# spacecam.net
KiCad netlist of a schematic drawn in EAGLE
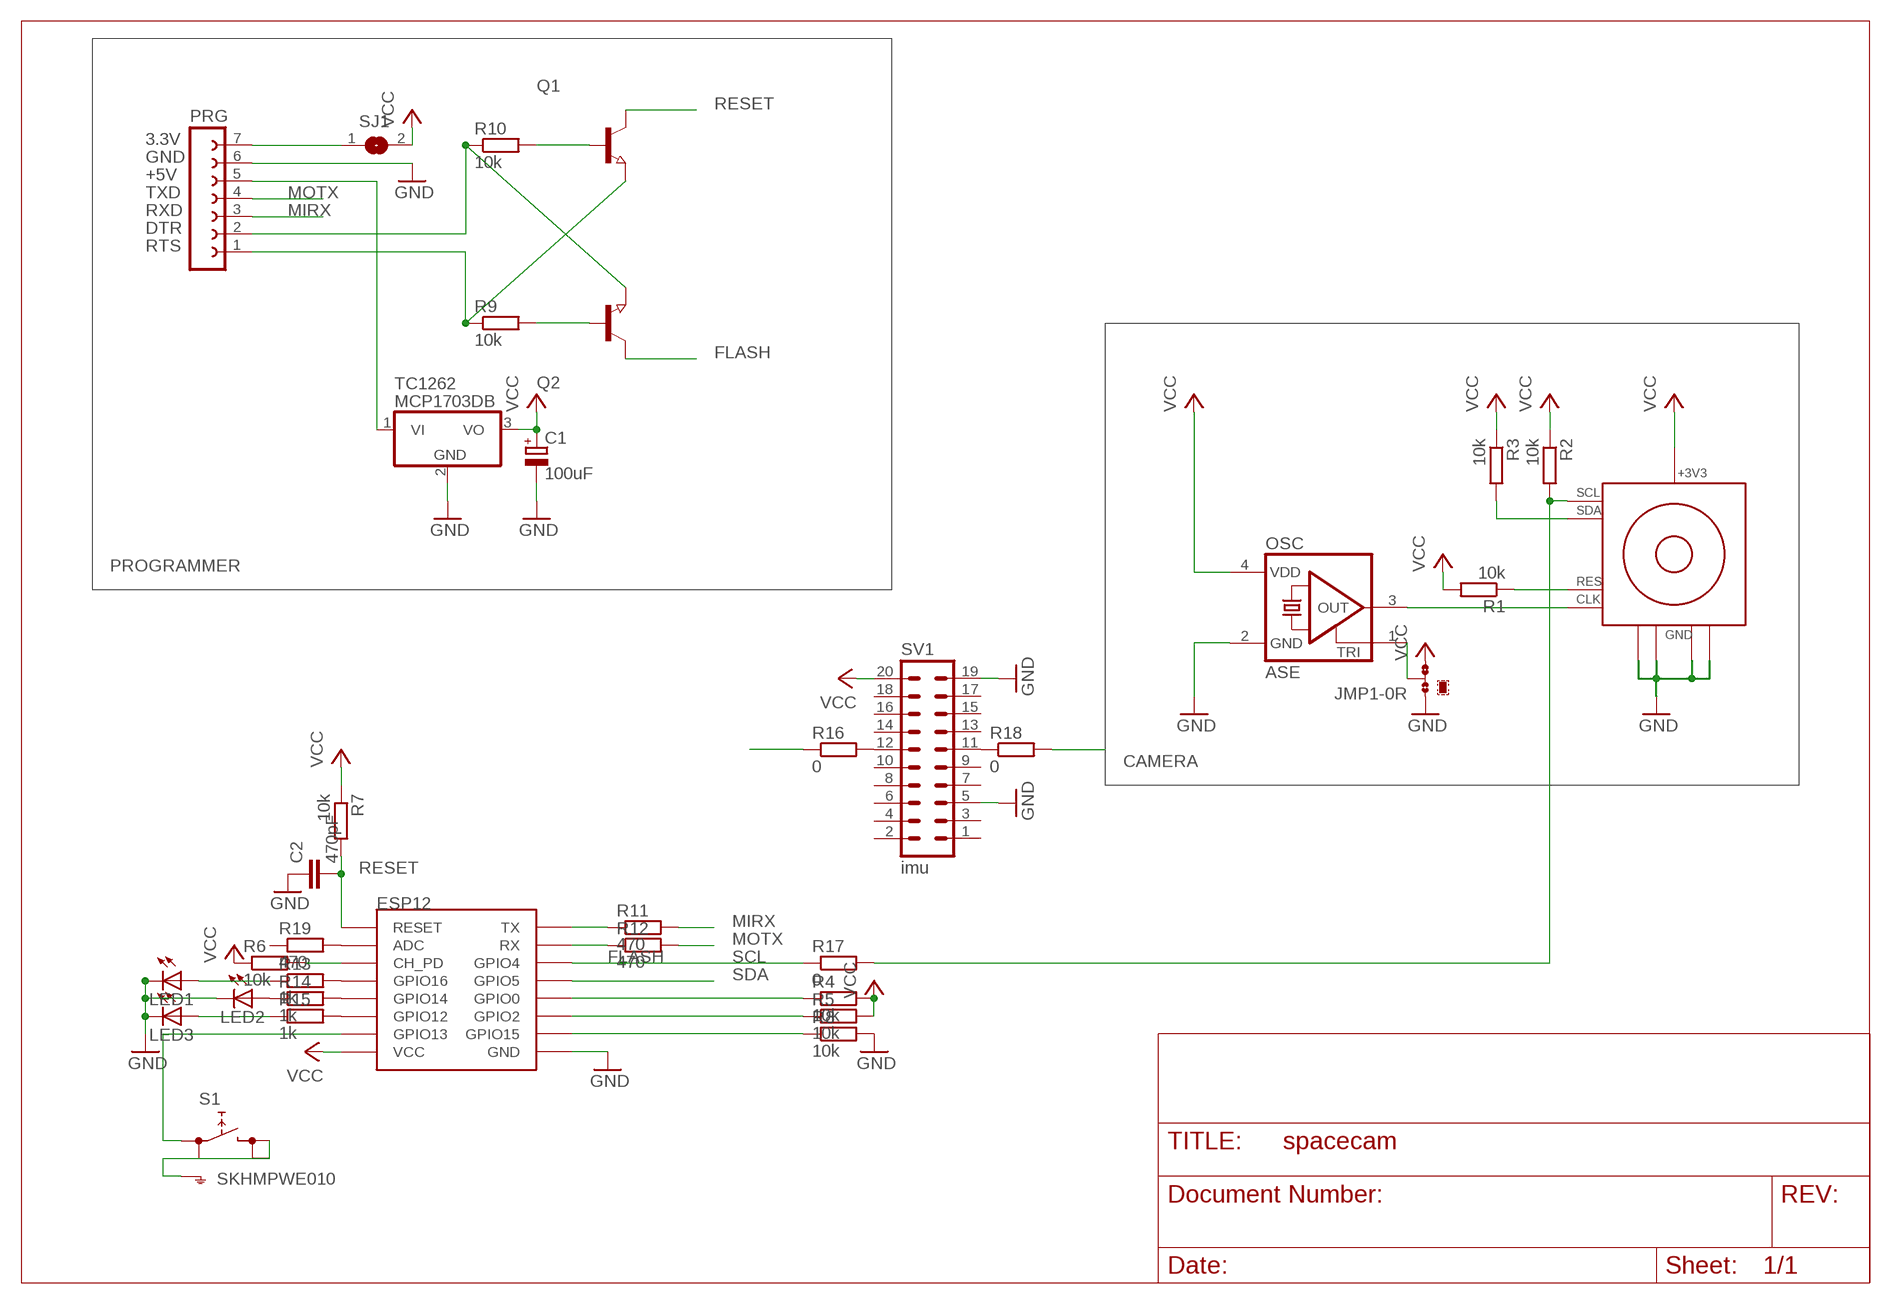
[diagram p0: schematic, sheet 1]

(export (version "E")
  (design (tool "Eeschema 10.0.6"))
  (components
    (comp (ref "C1")
      (value "100uF")
      (footprint "eagle-import:153CLV-0605")
      (libsource (lib "eagle-import") (part "CPOL-EU153CLV-0605"))
    )
    (comp (ref "C2")
      (value "470pF")
      (footprint "eagle-import:C0603")
      (libsource (lib "eagle-import") (part "C-EUC0603"))
    )
    (comp (ref "ESP12")
      (value "ESP12SMD")
      (footprint "eagle-import:ESP12-SMD")
      (libsource (lib "eagle-import") (part "ESP12SMD"))
    )
    (comp (ref "IR1")
      (value "Wiimote IR")
      (footprint "eagle-import:WII_IR_SENSOR")
      (libsource (lib "eagle-import") (part "WII_IR_SENSOR"))
    )
    (comp (ref "JMP1")
      (value "0R-JUMPB")
      (footprint "eagle-import:B0R-JMP")
      (libsource (lib "eagle-import") (part "0R-JUMPB"))
    )
    (comp (ref "LED1")
      (value "LEDSML0603")
      (footprint "eagle-import:SML0603")
      (libsource (lib "eagle-import") (part "LEDSML0603"))
    )
    (comp (ref "LED2")
      (value "LEDSML0603")
      (footprint "eagle-import:SML0603")
      (libsource (lib "eagle-import") (part "LEDSML0603"))
    )
    (comp (ref "LED3")
      (value "LEDSML0603")
      (footprint "eagle-import:SML0603")
      (libsource (lib "eagle-import") (part "LEDSML0603"))
    )
    (comp (ref "OSC")
      (value "ASE")
      (footprint "eagle-import:ASE")
      (libsource (lib "eagle-import") (part "ASE"))
    )
    (comp (ref "PRG")
      (value "FE07-1")
      (footprint "eagle-import:FE07")
      (libsource (lib "eagle-import") (part "FE07-1"))
    )
    (comp (ref "Q1")
      (value "NPN-TRANSISTOR_SOT23")
      (footprint "eagle-import:SOT23")
      (libsource (lib "eagle-import") (part "NPN-TRANSISTOR_SOT23"))
    )
    (comp (ref "Q2")
      (value "NPN-TRANSISTOR_SOT23")
      (footprint "eagle-import:SOT23")
      (libsource (lib "eagle-import") (part "NPN-TRANSISTOR_SOT23"))
    )
    (comp (ref "R1")
      (value "10k")
      (footprint "eagle-import:R0603")
      (libsource (lib "eagle-import") (part "R-EU_R0603"))
    )
    (comp (ref "R2")
      (value "10k")
      (footprint "eagle-import:R0603")
      (libsource (lib "eagle-import") (part "R-EU_R0603"))
    )
    (comp (ref "R3")
      (value "10k")
      (footprint "eagle-import:R0603")
      (libsource (lib "eagle-import") (part "R-EU_R0603"))
    )
    (comp (ref "R4")
      (value "10k")
      (footprint "eagle-import:R0603")
      (libsource (lib "eagle-import") (part "R-EU_R0603"))
    )
    (comp (ref "R5")
      (value "10k")
      (footprint "eagle-import:R0603")
      (libsource (lib "eagle-import") (part "R-EU_R0603"))
    )
    (comp (ref "R6")
      (value "10k")
      (footprint "eagle-import:R0603")
      (libsource (lib "eagle-import") (part "R-EU_R0603"))
    )
    (comp (ref "R7")
      (value "10k")
      (footprint "eagle-import:R0603")
      (libsource (lib "eagle-import") (part "R-EU_R0603"))
    )
    (comp (ref "R8")
      (value "10k")
      (footprint "eagle-import:R0603")
      (libsource (lib "eagle-import") (part "R-EU_R0603"))
    )
    (comp (ref "R9")
      (value "10k")
      (footprint "eagle-import:R0603")
      (libsource (lib "eagle-import") (part "R-EU_R0603"))
    )
    (comp (ref "R10")
      (value "10k")
      (footprint "eagle-import:R0603")
      (libsource (lib "eagle-import") (part "R-EU_R0603"))
    )
    (comp (ref "R11")
      (value "470")
      (footprint "eagle-import:R0603")
      (libsource (lib "eagle-import") (part "R-EU_R0603"))
    )
    (comp (ref "R12")
      (value "470")
      (footprint "eagle-import:R0603")
      (libsource (lib "eagle-import") (part "R-EU_R0603"))
    )
    (comp (ref "R13")
      (value "1k")
      (footprint "eagle-import:R0603")
      (libsource (lib "eagle-import") (part "R-EU_R0603"))
    )
    (comp (ref "R14")
      (value "1k")
      (footprint "eagle-import:R0603")
      (libsource (lib "eagle-import") (part "R-EU_R0603"))
    )
    (comp (ref "R15")
      (value "1k")
      (footprint "eagle-import:R0603")
      (libsource (lib "eagle-import") (part "R-EU_R0603"))
    )
    (comp (ref "R16")
      (value "0")
      (footprint "eagle-import:R0603")
      (libsource (lib "eagle-import") (part "R-EU_R0603"))
    )
    (comp (ref "R17")
      (value "0")
      (footprint "eagle-import:R0603")
      (libsource (lib "eagle-import") (part "R-EU_R0603"))
    )
    (comp (ref "R18")
      (value "0")
      (footprint "eagle-import:R0603")
      (libsource (lib "eagle-import") (part "R-EU_R0603"))
    )
    (comp (ref "R19")
      (value "470")
      (footprint "eagle-import:R0603")
      (libsource (lib "eagle-import") (part "R-EU_R0603"))
    )
    (comp (ref "S1")
      (value "SKHMPWE010")
      (footprint "eagle-import:SKHMPXE010")
      (libsource (lib "eagle-import") (part "SKHMPE010W"))
    )
    (comp (ref "SJ1") (value "SJ") (footprint "eagle-import:SJ") (libsource (lib "eagle-import") (part "SJ")))
    (comp (ref "SV1")
      (value "imu")
      (footprint "eagle-import:MA10-2")
      (libsource (lib "eagle-import") (part "MA10-2"))
    )
    (comp (ref "TC1262")
      (value "MCP1703DB")
      (footprint "eagle-import:SOT223")
      (libsource (lib "eagle-import") (part "MCP1703DB"))
    )
  )
  (nets
    (net (code "1") (name "/FLASH") (class "Default")
      (node (ref "ESP12") (pin "GPIO0") (pinfunction "GPIO0_GPIO0") (pintype "bidirectional"))
      (node (ref "Q2") (pin "3") (pinfunction "C_3") (pintype "passive"))
      (node (ref "R4") (pin "1") (pinfunction "1_1") (pintype "passive"))
    )
    (net (code "2") (name "/MIRX") (class "Default")
      (node (ref "PRG") (pin "3") (pinfunction "3_3") (pintype "passive"))
      (node (ref "R11") (pin "2") (pinfunction "2_2") (pintype "passive"))
    )
    (net (code "3") (name "/MOTX") (class "Default")
      (node (ref "PRG") (pin "4") (pinfunction "4_4") (pintype "passive"))
      (node (ref "R12") (pin "2") (pinfunction "2_2") (pintype "passive"))
    )
    (net (code "4") (name "/RESET") (class "Default")
      (node (ref "C2") (pin "2") (pinfunction "2_2") (pintype "passive"))
      (node (ref "ESP12") (pin "RESET") (pinfunction "RESET_RESET") (pintype "bidirectional"))
      (node (ref "Q1") (pin "3") (pinfunction "C_3") (pintype "passive"))
      (node (ref "R7") (pin "2") (pinfunction "2_2") (pintype "passive"))
    )
    (net (code "5") (name "/SCL") (class "Default")
      (node (ref "ESP12") (pin "GPIO4") (pinfunction "GPIO4_GPIO4") (pintype "bidirectional"))
      (node (ref "R16") (pin "1") (pinfunction "1_1") (pintype "passive"))
      (node (ref "R17") (pin "1") (pinfunction "1_1") (pintype "passive"))
    )
    (net (code "6") (name "/SDA") (class "Default")
      (node (ref "ESP12") (pin "GPIO5") (pinfunction "GPIO5_GPIO5") (pintype "bidirectional"))
      (node (ref "IR1") (pin "6_SDA") (pinfunction "SDA_6_SDA") (pintype "bidirectional"))
      (node (ref "R18") (pin "2") (pinfunction "2_2") (pintype "passive"))
      (node (ref "R3") (pin "2") (pinfunction "2_2") (pintype "passive"))
    )
    (net (code "7") (name "GND") (class "Default")
      (node (ref "C1") (pin "-") (pinfunction "-_-") (pintype "passive"))
      (node (ref "C2") (pin "1") (pinfunction "1_1") (pintype "passive"))
      (node (ref "ESP12") (pin "GND") (pinfunction "GND_GND") (pintype "bidirectional"))
      (node (ref "IR1") (pin "2_GND@1") (pinfunction "GND_2_GND@1") (pintype "bidirectional"))
      (node (ref "IR1") (pin "3_GND@2") (pinfunction "GND_3_GND@2") (pintype "bidirectional"))
      (node (ref "IR1") (pin "GND@3") (pinfunction "GND_GND@3") (pintype "bidirectional"))
      (node (ref "IR1") (pin "GND@4") (pinfunction "GND_GND@4") (pintype "bidirectional"))
      (node (ref "JMP1") (pin "1") (pinfunction "1_1") (pintype "passive"))
      (node (ref "LED1") (pin "C") (pinfunction "C_C") (pintype "passive"))
      (node (ref "LED2") (pin "C") (pinfunction "C_C") (pintype "passive"))
      (node (ref "LED3") (pin "C") (pinfunction "C_C") (pintype "passive"))
      (node (ref "OSC") (pin "2") (pinfunction "GND_2") (pintype "power_in"))
      (node (ref "PRG") (pin "6") (pinfunction "6_6") (pintype "passive"))
      (node (ref "R8") (pin "2") (pinfunction "2_2") (pintype "passive"))
      (node (ref "S1") (pin "2") (pinfunction "1.2_2") (pintype "passive"))
      (node (ref "S1") (pin "3") (pinfunction "2.1_3") (pintype "passive"))
      (node (ref "S1") (pin "4") (pinfunction "2.2_4") (pintype "passive"))
      (node (ref "S1") (pin "5") (pinfunction "SH_5") (pintype "passive"))
      (node (ref "SV1") (pin "19") (pinfunction "19_19") (pintype "passive"))
      (node (ref "SV1") (pin "5") (pinfunction "5_5") (pintype "passive"))
      (node (ref "TC1262") (pin "2") (pinfunction "GND_2") (pintype "passive"))
    )
    (net (code "8") (name "Net-(ESP12-PadADC)") (class "Default")
      (node (ref "ESP12") (pin "ADC") (pinfunction "ADC_ADC") (pintype "bidirectional"))
      (node (ref "R19") (pin "2") (pinfunction "2_2") (pintype "passive"))
    )
    (net (code "9") (name "Net-(ESP12-PadCH_PD)") (class "Default")
      (node (ref "ESP12") (pin "CH_PD") (pinfunction "CH_PD_CH_PD") (pintype "bidirectional"))
      (node (ref "R6") (pin "2") (pinfunction "2_2") (pintype "passive"))
    )
    (net (code "10") (name "Net-(ESP12-PadGPIO2)") (class "Default")
      (node (ref "ESP12") (pin "GPIO2") (pinfunction "GPIO2_GPIO2") (pintype "bidirectional"))
      (node (ref "R5") (pin "1") (pinfunction "1_1") (pintype "passive"))
    )
    (net (code "11") (name "Net-(ESP12-PadGPIO12)") (class "Default")
      (node (ref "ESP12") (pin "GPIO12") (pinfunction "GPIO12_GPIO12") (pintype "bidirectional"))
      (node (ref "R15") (pin "2") (pinfunction "2_2") (pintype "passive"))
    )
    (net (code "12") (name "Net-(ESP12-PadGPIO14)") (class "Default")
      (node (ref "ESP12") (pin "GPIO14") (pinfunction "GPIO14_GPIO14") (pintype "bidirectional"))
      (node (ref "R14") (pin "2") (pinfunction "2_2") (pintype "passive"))
    )
    (net (code "13") (name "Net-(ESP12-PadGPIO15)") (class "Default")
      (node (ref "ESP12") (pin "GPIO15") (pinfunction "GPIO15_GPIO15") (pintype "bidirectional"))
      (node (ref "R8") (pin "1") (pinfunction "1_1") (pintype "passive"))
    )
    (net (code "14") (name "Net-(ESP12-PadGPIO16)") (class "Default")
      (node (ref "ESP12") (pin "GPIO16") (pinfunction "GPIO16_GPIO16") (pintype "bidirectional"))
      (node (ref "R13") (pin "2") (pinfunction "2_2") (pintype "passive"))
    )
    (net (code "15") (name "Net-(ESP12-RX)") (class "Default")
      (node (ref "ESP12") (pin "RXD0") (pinfunction "RX_RXD0") (pintype "bidirectional"))
      (node (ref "R12") (pin "1") (pinfunction "1_1") (pintype "passive"))
    )
    (net (code "16") (name "Net-(ESP12-TX)") (class "Default")
      (node (ref "ESP12") (pin "TXD0") (pinfunction "TX_TXD0") (pintype "bidirectional"))
      (node (ref "R11") (pin "1") (pinfunction "1_1") (pintype "passive"))
    )
    (net (code "17") (name "Net-(IR1-CLK)") (class "Default")
      (node (ref "IR1") (pin "7_CLK") (pinfunction "CLK_7_CLK") (pintype "bidirectional"))
      (node (ref "OSC") (pin "3") (pinfunction "OUT_3") (pintype "output"))
    )
    (net (code "18") (name "Net-(IR1-RES)") (class "Default")
      (node (ref "IR1") (pin "8_RESET") (pinfunction "RES_8_RESET") (pintype "bidirectional"))
      (node (ref "R1") (pin "1") (pinfunction "1_1") (pintype "passive"))
    )
    (net (code "19") (name "Net-(IR1-SCL)") (class "Default")
      (node (ref "IR1") (pin "5_SCL") (pinfunction "SCL_5_SCL") (pintype "bidirectional"))
      (node (ref "R17") (pin "2") (pinfunction "2_2") (pintype "passive"))
      (node (ref "R2") (pin "2") (pinfunction "2_2") (pintype "passive"))
    )
    (net (code "20") (name "Net-(LED1-PadA)") (class "Default")
      (node (ref "LED1") (pin "A") (pinfunction "A_A") (pintype "passive"))
      (node (ref "R13") (pin "1") (pinfunction "1_1") (pintype "passive"))
    )
    (net (code "21") (name "Net-(LED2-PadA)") (class "Default")
      (node (ref "LED2") (pin "A") (pinfunction "A_A") (pintype "passive"))
      (node (ref "R14") (pin "1") (pinfunction "1_1") (pintype "passive"))
    )
    (net (code "22") (name "Net-(LED3-PadA)") (class "Default")
      (node (ref "LED3") (pin "A") (pinfunction "A_A") (pintype "passive"))
      (node (ref "R15") (pin "1") (pinfunction "1_1") (pintype "passive"))
    )
    (net (code "23") (name "Net-(OSC-TRI)") (class "Default")
      (node (ref "JMP1") (pin "2") (pinfunction "2_2") (pintype "passive"))
      (node (ref "OSC") (pin "1") (pinfunction "TRI_1") (pintype "input"))
    )
    (net (code "24") (name "Net-(PRG-Pad7)") (class "Default")
      (node (ref "PRG") (pin "7") (pinfunction "7_7") (pintype "passive"))
      (node (ref "SJ1") (pin "1") (pinfunction "1_1") (pintype "passive"))
    )
    (net (code "25") (name "Net-(Q1-B)") (class "Default")
      (node (ref "Q1") (pin "1") (pinfunction "B_1") (pintype "passive"))
      (node (ref "R10") (pin "2") (pinfunction "2_2") (pintype "passive"))
    )
    (net (code "26") (name "Net-(Q1-E)") (class "Default")
      (node (ref "PRG") (pin "1") (pinfunction "1_1") (pintype "passive"))
      (node (ref "Q1") (pin "2") (pinfunction "E_2") (pintype "passive"))
      (node (ref "R9") (pin "1") (pinfunction "1_1") (pintype "passive"))
    )
    (net (code "27") (name "Net-(Q2-B)") (class "Default")
      (node (ref "Q2") (pin "1") (pinfunction "B_1") (pintype "passive"))
      (node (ref "R9") (pin "2") (pinfunction "2_2") (pintype "passive"))
    )
    (net (code "28") (name "Net-(Q2-E)") (class "Default")
      (node (ref "PRG") (pin "2") (pinfunction "2_2") (pintype "passive"))
      (node (ref "Q2") (pin "2") (pinfunction "E_2") (pintype "passive"))
      (node (ref "R10") (pin "1") (pinfunction "1_1") (pintype "passive"))
    )
    (net (code "29") (name "Net-(R16-Pad2)") (class "Default")
      (node (ref "R16") (pin "2") (pinfunction "2_2") (pintype "passive"))
      (node (ref "SV1") (pin "12") (pinfunction "12_12") (pintype "passive"))
    )
    (net (code "30") (name "Net-(R18-Pad1)") (class "Default")
      (node (ref "R18") (pin "1") (pinfunction "1_1") (pintype "passive"))
      (node (ref "SV1") (pin "11") (pinfunction "11_11") (pintype "passive"))
    )
    (net (code "31") (name "Net-(S1-1.1)") (class "Default")
      (node (ref "ESP12") (pin "GPIO13") (pinfunction "GPIO13_GPIO13") (pintype "bidirectional"))
      (node (ref "S1") (pin "1") (pinfunction "1.1_1") (pintype "passive"))
    )
    (net (code "32") (name "Net-(TC1262-VI)") (class "Default")
      (node (ref "PRG") (pin "5") (pinfunction "5_5") (pintype "passive"))
      (node (ref "TC1262") (pin "1") (pinfunction "VI_1") (pintype "input"))
    )
    (net (code "33") (name "VCC") (class "Default")
      (node (ref "C1") (pin "+") (pinfunction "+_+") (pintype "passive"))
      (node (ref "ESP12") (pin "VCC") (pinfunction "VCC_VCC") (pintype "bidirectional"))
      (node (ref "IR1") (pin "1_+3V3") (pinfunction "+3V3_1_+3V3") (pintype "bidirectional"))
      (node (ref "JMP1") (pin "3") (pinfunction "3_3") (pintype "passive"))
      (node (ref "OSC") (pin "4") (pinfunction "VDD_4") (pintype "power_in"))
      (node (ref "R1") (pin "2") (pinfunction "2_2") (pintype "passive"))
      (node (ref "R2") (pin "1") (pinfunction "1_1") (pintype "passive"))
      (node (ref "R3") (pin "1") (pinfunction "1_1") (pintype "passive"))
      (node (ref "R4") (pin "2") (pinfunction "2_2") (pintype "passive"))
      (node (ref "R5") (pin "2") (pinfunction "2_2") (pintype "passive"))
      (node (ref "R6") (pin "1") (pinfunction "1_1") (pintype "passive"))
      (node (ref "R7") (pin "1") (pinfunction "1_1") (pintype "passive"))
      (node (ref "SJ1") (pin "2") (pinfunction "2_2") (pintype "passive"))
      (node (ref "SV1") (pin "20") (pinfunction "20_20") (pintype "passive"))
      (node (ref "TC1262") (pin "3") (pinfunction "VO_3") (pintype "passive"))
    )
    (net (code "34") (name "unconnected-(R19-Pad1)") (class "Default")
      (node (ref "R19") (pin "1") (pinfunction "1_1") (pintype "passive"))
    )
    (net (code "35") (name "unconnected-(SV1-Pad1)") (class "Default")
      (node (ref "SV1") (pin "1") (pinfunction "1_1") (pintype "passive"))
    )
    (net (code "36") (name "unconnected-(SV1-Pad2)") (class "Default")
      (node (ref "SV1") (pin "2") (pinfunction "2_2") (pintype "passive"))
    )
    (net (code "37") (name "unconnected-(SV1-Pad3)") (class "Default")
      (node (ref "SV1") (pin "3") (pinfunction "3_3") (pintype "passive"))
    )
    (net (code "38") (name "unconnected-(SV1-Pad4)") (class "Default")
      (node (ref "SV1") (pin "4") (pinfunction "4_4") (pintype "passive"))
    )
    (net (code "39") (name "unconnected-(SV1-Pad6)") (class "Default")
      (node (ref "SV1") (pin "6") (pinfunction "6_6") (pintype "passive"))
    )
    (net (code "40") (name "unconnected-(SV1-Pad7)") (class "Default")
      (node (ref "SV1") (pin "7") (pinfunction "7_7") (pintype "passive"))
    )
    (net (code "41") (name "unconnected-(SV1-Pad8)") (class "Default")
      (node (ref "SV1") (pin "8") (pinfunction "8_8") (pintype "passive"))
    )
    (net (code "42") (name "unconnected-(SV1-Pad9)") (class "Default")
      (node (ref "SV1") (pin "9") (pinfunction "9_9") (pintype "passive"))
    )
    (net (code "43") (name "unconnected-(SV1-Pad10)") (class "Default")
      (node (ref "SV1") (pin "10") (pinfunction "10_10") (pintype "passive"))
    )
    (net (code "44") (name "unconnected-(SV1-Pad13)") (class "Default")
      (node (ref "SV1") (pin "13") (pinfunction "13_13") (pintype "passive"))
    )
    (net (code "45") (name "unconnected-(SV1-Pad14)") (class "Default")
      (node (ref "SV1") (pin "14") (pinfunction "14_14") (pintype "passive"))
    )
    (net (code "46") (name "unconnected-(SV1-Pad15)") (class "Default")
      (node (ref "SV1") (pin "15") (pinfunction "15_15") (pintype "passive"))
    )
    (net (code "47") (name "unconnected-(SV1-Pad16)") (class "Default")
      (node (ref "SV1") (pin "16") (pinfunction "16_16") (pintype "passive"))
    )
    (net (code "48") (name "unconnected-(SV1-Pad17)") (class "Default")
      (node (ref "SV1") (pin "17") (pinfunction "17_17") (pintype "passive"))
    )
    (net (code "49") (name "unconnected-(SV1-Pad18)") (class "Default")
      (node (ref "SV1") (pin "18") (pinfunction "18_18") (pintype "passive"))
    )
  )
)
